# OmneticsAdaptorSingleHeadstage.net
KiCad netlist of a schematic drawn in EAGLE
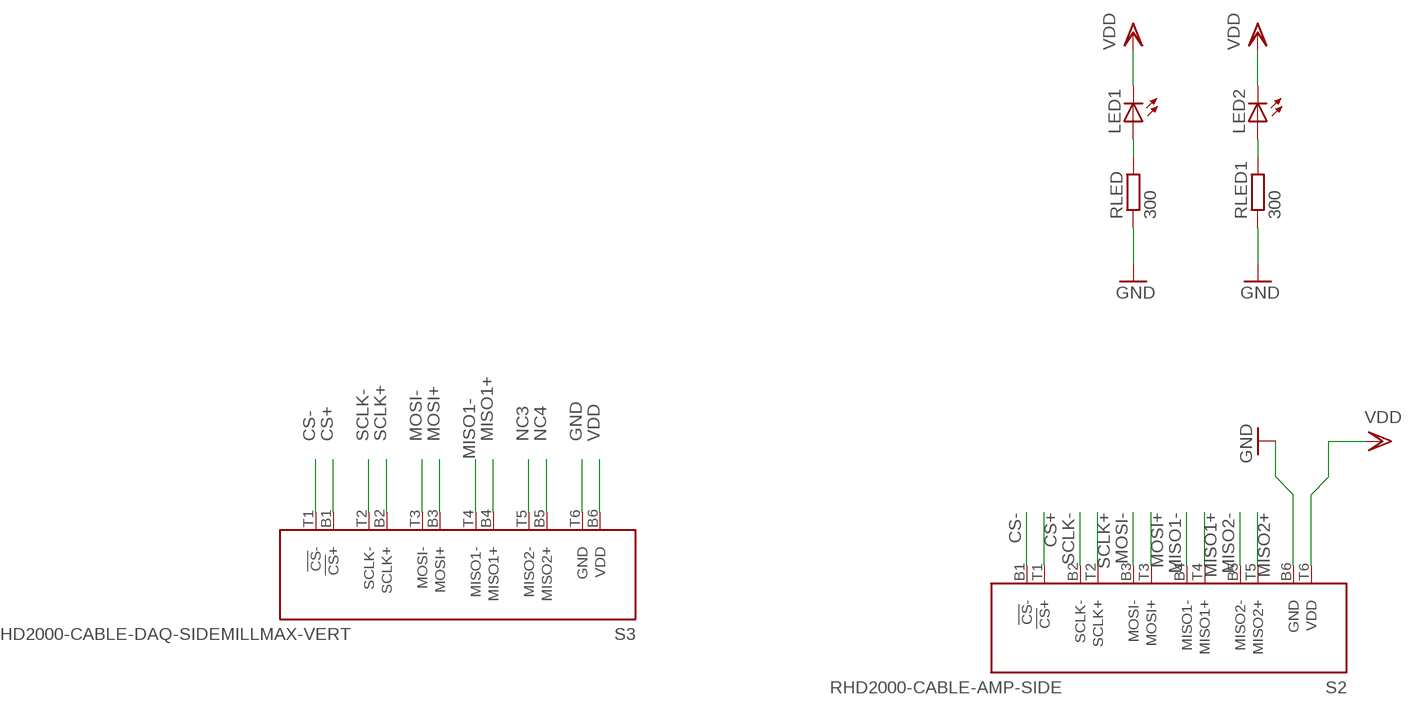
[diagram p0: schematic, sheet 1]

(export (version "E")
  (design (tool "Eeschema 10.0.6"))
  (components
    (comp (ref "LED1")
      (value "LEDCHIPLED_0805")
      (footprint "eagle-import:CHIPLED_0805")
      (libsource (lib "eagle-import") (part "LEDCHIPLED_0805"))
    )
    (comp (ref "LED2")
      (value "LEDCHIPLED_0805")
      (footprint "eagle-import:CHIPLED_0805")
      (libsource (lib "eagle-import") (part "LEDCHIPLED_0805"))
    )
    (comp (ref "RLED")
      (value "300")
      (footprint "eagle-import:R0402")
      (libsource (lib "eagle-import") (part "R-EU_R0402"))
    )
    (comp (ref "RLED1")
      (value "300")
      (footprint "eagle-import:R0402")
      (libsource (lib "eagle-import") (part "R-EU_R0402"))
    )
    (comp (ref "S2")
      (value "RHD2000-CABLE-AMP-SIDE")
      (footprint "eagle-import:OMNETICS_PZN-12-AA")
      (libsource (lib "eagle-import") (part "RHD2000-CABLE-AMP-SIDE"))
    )
    (comp (ref "S3")
      (value "RHD2000-CABLE-DAQ-SIDEMILLMAX-VERT")
      (footprint "eagle-import:MILLMAX-12PIN-VERT")
      (libsource (lib "eagle-import") (part "RHD2000-CABLE-DAQ-SIDEMILLMAX-VERT"))
    )
  )
  (nets
    (net (code "1") (name "/CS+") (class "Default")
      (node (ref "S2") (pin "T1") (pinfunction "~{CS}+_T1") (pintype "bidirectional"))
      (node (ref "S3") (pin "B1") (pinfunction "~{CS}+_B1") (pintype "bidirectional"))
    )
    (net (code "2") (name "/CS-") (class "Default")
      (node (ref "S2") (pin "B1") (pinfunction "~{CS}-_B1") (pintype "bidirectional"))
      (node (ref "S3") (pin "T1") (pinfunction "~{CS}-_T1") (pintype "bidirectional"))
    )
    (net (code "3") (name "/MISO1+") (class "Default")
      (node (ref "S2") (pin "T4") (pinfunction "MISO1+_T4") (pintype "bidirectional"))
      (node (ref "S3") (pin "B4") (pinfunction "MISO1+_B4") (pintype "bidirectional"))
    )
    (net (code "4") (name "/MISO1-") (class "Default")
      (node (ref "S2") (pin "B4") (pinfunction "MISO1-_B4") (pintype "bidirectional"))
      (node (ref "S3") (pin "T4") (pinfunction "MISO1-_T4") (pintype "bidirectional"))
    )
    (net (code "5") (name "/MISO2+") (class "Default")
      (node (ref "S2") (pin "T5") (pinfunction "MISO2+_T5") (pintype "bidirectional"))
    )
    (net (code "6") (name "/MISO2-") (class "Default")
      (node (ref "S2") (pin "B5") (pinfunction "MISO2-_B5") (pintype "bidirectional"))
    )
    (net (code "7") (name "/MOSI+") (class "Default")
      (node (ref "S2") (pin "T3") (pinfunction "MOSI+_T3") (pintype "bidirectional"))
      (node (ref "S3") (pin "B3") (pinfunction "MOSI+_B3") (pintype "bidirectional"))
    )
    (net (code "8") (name "/MOSI-") (class "Default")
      (node (ref "S2") (pin "B3") (pinfunction "MOSI-_B3") (pintype "bidirectional"))
      (node (ref "S3") (pin "T3") (pinfunction "MOSI-_T3") (pintype "bidirectional"))
    )
    (net (code "9") (name "/NC3") (class "Default")
      (node (ref "S3") (pin "T5") (pinfunction "MISO2-_T5") (pintype "bidirectional"))
    )
    (net (code "10") (name "/NC4") (class "Default")
      (node (ref "S3") (pin "B5") (pinfunction "MISO2+_B5") (pintype "bidirectional"))
    )
    (net (code "11") (name "/SCLK+") (class "Default")
      (node (ref "S2") (pin "T2") (pinfunction "SCLK+_T2") (pintype "bidirectional"))
      (node (ref "S3") (pin "B2") (pinfunction "SCLK+_B2") (pintype "bidirectional"))
    )
    (net (code "12") (name "/SCLK-") (class "Default")
      (node (ref "S2") (pin "B2") (pinfunction "SCLK-_B2") (pintype "bidirectional"))
      (node (ref "S3") (pin "T2") (pinfunction "SCLK-_T2") (pintype "bidirectional"))
    )
    (net (code "13") (name "GND") (class "Default")
      (node (ref "RLED") (pin "1") (pinfunction "1_1") (pintype "passive"))
      (node (ref "RLED1") (pin "1") (pinfunction "1_1") (pintype "passive"))
      (node (ref "S2") (pin "B6") (pinfunction "GND_B6") (pintype "power_in"))
      (node (ref "S3") (pin "T6") (pinfunction "GND_T6") (pintype "power_in"))
    )
    (net (code "14") (name "Net-(LED1-PadA)") (class "Default")
      (node (ref "LED1") (pin "A") (pinfunction "A_A") (pintype "passive"))
      (node (ref "RLED") (pin "2") (pinfunction "2_2") (pintype "passive"))
    )
    (net (code "15") (name "Net-(LED2-PadA)") (class "Default")
      (node (ref "LED2") (pin "A") (pinfunction "A_A") (pintype "passive"))
      (node (ref "RLED1") (pin "2") (pinfunction "2_2") (pintype "passive"))
    )
    (net (code "16") (name "VDD") (class "Default")
      (node (ref "LED1") (pin "C") (pinfunction "C_C") (pintype "passive"))
      (node (ref "LED2") (pin "C") (pinfunction "C_C") (pintype "passive"))
      (node (ref "S2") (pin "T6") (pinfunction "VDD_T6") (pintype "bidirectional"))
      (node (ref "S3") (pin "B6") (pinfunction "VDD_B6") (pintype "bidirectional"))
    )
  )
)
